# DC_DRIVERS.net
KiCad netlist of a schematic drawn in Altium Designer
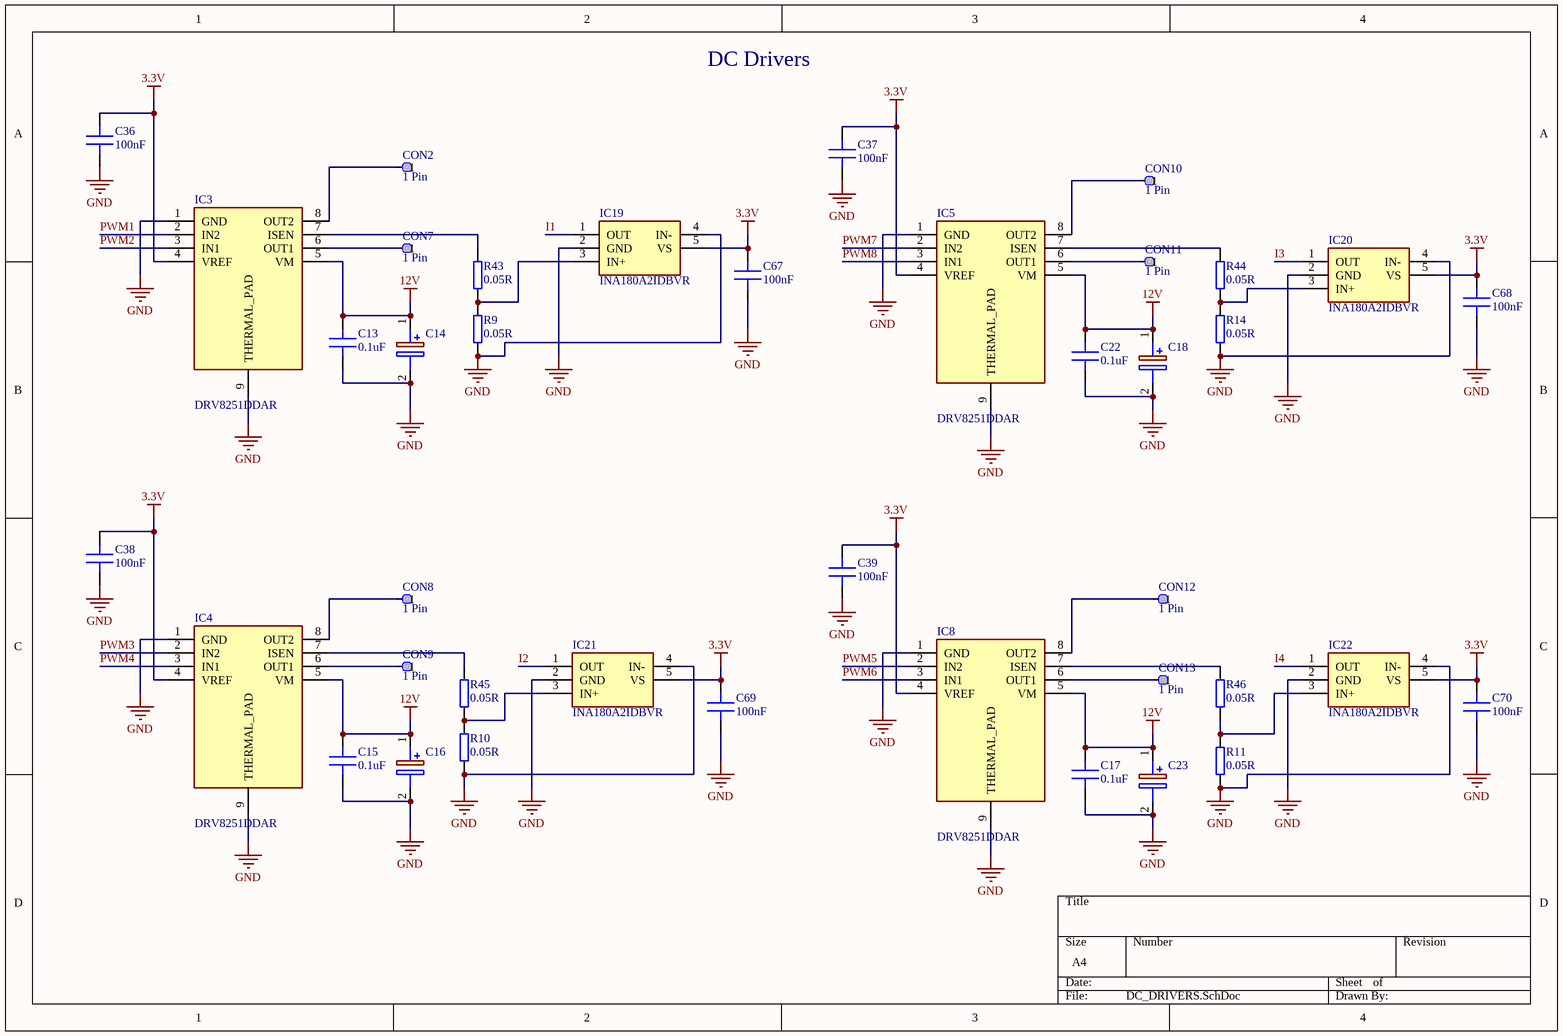
[diagram p0: DC_DRIVERS.SchDoc]

(export (version "E")
  (design (tool "Eeschema 10.0.6"))
  (components
    (comp (ref "C13")
      (value "0.1uF")
      (footprint "C 0402")
      (description "MLCC Capacitor")
      (libsource (lib "Components") (part "Capacitor"))
    )
    (comp (ref "C14")
      (value "UVY1V101MED1TD")
      (footprint "SamacSys:CAPPRD250W50D655H1250")
      (description "Capacitor Polarised")
      (libsource (lib "caravan_sch_lib") (part "UVY1V101MED1TD"))
    )
    (comp (ref "C15")
      (value "0.1uF")
      (footprint "C 0603")
      (description "MLCC Capacitor")
      (libsource (lib "Components") (part "Capacitor"))
    )
    (comp (ref "C16")
      (value "UVY1V101MED1TD")
      (footprint "SamacSys:CAPPRD250W50D655H1250")
      (description "Capacitor Polarised")
      (libsource (lib "caravan_sch_lib") (part "UVY1V101MED1TD"))
    )
    (comp (ref "C17")
      (value "0.1uF")
      (footprint "C 0402")
      (description "MLCC Capacitor")
      (libsource (lib "Components") (part "Capacitor"))
    )
    (comp (ref "C18")
      (value "UVY1V101MED1TD")
      (footprint "SamacSys:CAPPRD250W50D655H1250")
      (description "Capacitor Polarised")
      (libsource (lib "caravan_sch_lib") (part "UVY1V101MED1TD"))
    )
    (comp (ref "C22")
      (value "0.1uF")
      (footprint "C 0402")
      (description "MLCC Capacitor")
      (libsource (lib "Components") (part "Capacitor"))
    )
    (comp (ref "C23")
      (value "UVY1V101MED1TD")
      (footprint "SamacSys:CAPPRD250W50D655H1250")
      (description "Capacitor Polarised")
      (libsource (lib "caravan_sch_lib") (part "UVY1V101MED1TD"))
    )
    (comp (ref "C36")
      (value "100nF")
      (footprint "C 0402")
      (description "MLCC Capacitor")
      (libsource (lib "Components") (part "Capacitor"))
    )
    (comp (ref "C37")
      (value "100nF")
      (footprint "C 0402")
      (description "MLCC Capacitor")
      (libsource (lib "Components") (part "Capacitor"))
    )
    (comp (ref "C38")
      (value "100nF")
      (footprint "C 0402")
      (description "MLCC Capacitor")
      (libsource (lib "Components") (part "Capacitor"))
    )
    (comp (ref "C39")
      (value "100nF")
      (footprint "C 0402")
      (description "MLCC Capacitor")
      (libsource (lib "Components") (part "Capacitor"))
    )
    (comp (ref "C67")
      (value "100nF")
      (footprint "C 0402")
      (description "MLCC Capacitor")
      (libsource (lib "Components") (part "Capacitor"))
    )
    (comp (ref "C68")
      (value "100nF")
      (footprint "C 0402")
      (description "MLCC Capacitor")
      (libsource (lib "Components") (part "Capacitor"))
    )
    (comp (ref "C69")
      (value "100nF")
      (footprint "C 0402")
      (description "MLCC Capacitor")
      (libsource (lib "Components") (part "Capacitor"))
    )
    (comp (ref "C70")
      (value "100nF")
      (footprint "C 0402")
      (description "MLCC Capacitor")
      (libsource (lib "Components") (part "Capacitor"))
    )
    (comp (ref "CON2") (value "1 Pin") (footprint "SMD PAD") (libsource (lib "Connectors") (part "1 Pin")))
    (comp (ref "CON7") (value "1 Pin") (footprint "SMD PAD") (libsource (lib "Connectors") (part "1 Pin")))
    (comp (ref "CON8") (value "1 Pin") (footprint "SMD PAD") (libsource (lib "Connectors") (part "1 Pin")))
    (comp (ref "CON9") (value "1 Pin") (footprint "SMD PAD") (libsource (lib "Connectors") (part "1 Pin")))
    (comp (ref "CON10") (value "1 Pin") (footprint "SMD PAD") (libsource (lib "Connectors") (part "1 Pin")))
    (comp (ref "CON11") (value "1 Pin") (footprint "SMD PAD") (libsource (lib "Connectors") (part "1 Pin")))
    (comp (ref "CON12") (value "1 Pin") (footprint "SMD PAD") (libsource (lib "Connectors") (part "1 Pin")))
    (comp (ref "CON13") (value "1 Pin") (footprint "SMD PAD") (libsource (lib "Connectors") (part "1 Pin")))
    (comp (ref "IC3")
      (value "DRV8251DDAR")
      (footprint "SamacSys:SOIC127P600X170-9N")
      (description "Integrated Circuit")
      (fields (field (name "MOUSER PART NUMBER") "595-DRV8251DDAR"))
      (libsource (lib "caravan_sch_lib") (part "DRV8251DDAR"))
    )
    (comp (ref "IC4")
      (value "DRV8251DDAR")
      (footprint "SamacSys:SOIC127P600X170-9N")
      (description "Integrated Circuit")
      (fields (field (name "MOUSER PART NUMBER") "595-DRV8251DDAR"))
      (libsource (lib "caravan_sch_lib") (part "DRV8251DDAR"))
    )
    (comp (ref "IC5")
      (value "DRV8251DDAR")
      (footprint "SamacSys:SOIC127P600X170-9N")
      (description "Integrated Circuit")
      (fields (field (name "MOUSER PART NUMBER") "595-DRV8251DDAR"))
      (libsource (lib "caravan_sch_lib") (part "DRV8251DDAR"))
    )
    (comp (ref "IC8")
      (value "DRV8251DDAR")
      (footprint "SamacSys:SOIC127P600X170-9N")
      (description "Integrated Circuit")
      (fields (field (name "MOUSER PART NUMBER") "595-DRV8251DDAR"))
      (libsource (lib "caravan_sch_lib") (part "DRV8251DDAR"))
    )
    (comp (ref "IC19")
      (value "INA180A2IDBVR")
      (footprint "SamacSys:SOT95P280X145-5N")
      (description "Integrated Circuit")
      (fields (field (name "MOUSER PART NUMBER") "595-INA180A2IDBVR"))
      (libsource (lib "caravan_sch_lib") (part "INA180A2IDBVR"))
    )
    (comp (ref "IC20")
      (value "INA180A2IDBVR")
      (footprint "SamacSys:SOT95P280X145-5N")
      (description "Integrated Circuit")
      (fields (field (name "MOUSER PART NUMBER") "595-INA180A2IDBVR"))
      (libsource (lib "caravan_sch_lib") (part "INA180A2IDBVR"))
    )
    (comp (ref "IC21")
      (value "INA180A2IDBVR")
      (footprint "SamacSys:SOT95P280X145-5N")
      (description "Integrated Circuit")
      (fields (field (name "MOUSER PART NUMBER") "595-INA180A2IDBVR"))
      (libsource (lib "caravan_sch_lib") (part "INA180A2IDBVR"))
    )
    (comp (ref "IC22")
      (value "INA180A2IDBVR")
      (footprint "SamacSys:SOT95P280X145-5N")
      (description "Integrated Circuit")
      (fields (field (name "MOUSER PART NUMBER") "595-INA180A2IDBVR"))
      (libsource (lib "caravan_sch_lib") (part "INA180A2IDBVR"))
    )
    (comp (ref "R9")
      (value "0.05R")
      (footprint "R 1206")
      (description "General pourpouse resistor")
      (libsource (lib "Components") (part "Resistor"))
    )
    (comp (ref "R10")
      (value "0.05R")
      (footprint "R 1206")
      (description "General pourpouse resistor")
      (libsource (lib "Components") (part "Resistor"))
    )
    (comp (ref "R11")
      (value "0.05R")
      (footprint "R 1206")
      (description "General pourpouse resistor")
      (libsource (lib "Components") (part "Resistor"))
    )
    (comp (ref "R14")
      (value "0.05R")
      (footprint "R 1206")
      (description "General pourpouse resistor")
      (libsource (lib "Components") (part "Resistor"))
    )
    (comp (ref "R43")
      (value "0.05R")
      (footprint "R 1206")
      (description "General pourpouse resistor")
      (libsource (lib "Components") (part "Resistor"))
    )
    (comp (ref "R44")
      (value "0.05R")
      (footprint "R 1206")
      (description "General pourpouse resistor")
      (libsource (lib "Components") (part "Resistor"))
    )
    (comp (ref "R45")
      (value "0.05R")
      (footprint "R 1206")
      (description "General pourpouse resistor")
      (libsource (lib "Components") (part "Resistor"))
    )
    (comp (ref "R46")
      (value "0.05R")
      (footprint "R 1206")
      (description "General pourpouse resistor")
      (libsource (lib "Components") (part "Resistor"))
    )
  )
  (nets
    (net (code "1") (name "/I1") (class "Default")
      (node (ref "IC19") (pin "1") (pinfunction "OUT_1") (pintype "passive"))
    )
    (net (code "2") (name "/I2") (class "Default")
      (node (ref "IC21") (pin "1") (pinfunction "OUT_1") (pintype "passive"))
    )
    (net (code "3") (name "/I3") (class "Default")
      (node (ref "IC20") (pin "1") (pinfunction "OUT_1") (pintype "passive"))
    )
    (net (code "4") (name "/I4") (class "Default")
      (node (ref "IC22") (pin "1") (pinfunction "OUT_1") (pintype "passive"))
    )
    (net (code "5") (name "/PWM1") (class "Default")
      (node (ref "IC3") (pin "2") (pinfunction "IN2_2") (pintype "passive"))
    )
    (net (code "6") (name "/PWM2") (class "Default")
      (node (ref "IC3") (pin "3") (pinfunction "IN1_3") (pintype "passive"))
    )
    (net (code "7") (name "/PWM3") (class "Default")
      (node (ref "IC4") (pin "2") (pinfunction "IN2_2") (pintype "passive"))
    )
    (net (code "8") (name "/PWM4") (class "Default")
      (node (ref "IC4") (pin "3") (pinfunction "IN1_3") (pintype "passive"))
    )
    (net (code "9") (name "/PWM5") (class "Default")
      (node (ref "IC8") (pin "2") (pinfunction "IN2_2") (pintype "passive"))
    )
    (net (code "10") (name "/PWM6") (class "Default")
      (node (ref "IC8") (pin "3") (pinfunction "IN1_3") (pintype "passive"))
    )
    (net (code "11") (name "/PWM7") (class "Default")
      (node (ref "IC5") (pin "2") (pinfunction "IN2_2") (pintype "passive"))
    )
    (net (code "12") (name "/PWM8") (class "Default")
      (node (ref "IC5") (pin "3") (pinfunction "IN1_3") (pintype "passive"))
    )
    (net (code "13") (name "3.3V") (class "Default")
      (node (ref "C36") (pin "1") (pinfunction "1_1") (pintype "passive"))
      (node (ref "C37") (pin "1") (pinfunction "1_1") (pintype "passive"))
      (node (ref "C38") (pin "1") (pinfunction "1_1") (pintype "passive"))
      (node (ref "C39") (pin "1") (pinfunction "1_1") (pintype "passive"))
      (node (ref "C67") (pin "1") (pinfunction "1_1") (pintype "passive"))
      (node (ref "C68") (pin "1") (pinfunction "1_1") (pintype "passive"))
      (node (ref "C69") (pin "1") (pinfunction "1_1") (pintype "passive"))
      (node (ref "C70") (pin "1") (pinfunction "1_1") (pintype "passive"))
      (node (ref "IC19") (pin "5") (pinfunction "VS_5") (pintype "passive"))
      (node (ref "IC20") (pin "5") (pinfunction "VS_5") (pintype "passive"))
      (node (ref "IC21") (pin "5") (pinfunction "VS_5") (pintype "passive"))
      (node (ref "IC22") (pin "5") (pinfunction "VS_5") (pintype "passive"))
      (node (ref "IC3") (pin "4") (pinfunction "VREF_4") (pintype "passive"))
      (node (ref "IC4") (pin "4") (pinfunction "VREF_4") (pintype "passive"))
      (node (ref "IC5") (pin "4") (pinfunction "VREF_4") (pintype "passive"))
      (node (ref "IC8") (pin "4") (pinfunction "VREF_4") (pintype "passive"))
    )
    (net (code "14") (name "12V") (class "Default")
      (node (ref "C13") (pin "1") (pinfunction "1_1") (pintype "passive"))
      (node (ref "C14") (pin "1") (pinfunction "+_1") (pintype "passive"))
      (node (ref "C15") (pin "1") (pinfunction "1_1") (pintype "passive"))
      (node (ref "C16") (pin "1") (pinfunction "+_1") (pintype "passive"))
      (node (ref "C17") (pin "1") (pinfunction "1_1") (pintype "passive"))
      (node (ref "C18") (pin "1") (pinfunction "+_1") (pintype "passive"))
      (node (ref "C22") (pin "1") (pinfunction "1_1") (pintype "passive"))
      (node (ref "C23") (pin "1") (pinfunction "+_1") (pintype "passive"))
      (node (ref "IC3") (pin "5") (pinfunction "VM_5") (pintype "passive"))
      (node (ref "IC4") (pin "5") (pinfunction "VM_5") (pintype "passive"))
      (node (ref "IC5") (pin "5") (pinfunction "VM_5") (pintype "passive"))
      (node (ref "IC8") (pin "5") (pinfunction "VM_5") (pintype "passive"))
    )
    (net (code "15") (name "GND") (class "Default")
      (node (ref "C13") (pin "2") (pinfunction "2_2") (pintype "passive"))
      (node (ref "C14") (pin "2") (pinfunction "-_2") (pintype "passive"))
      (node (ref "C15") (pin "2") (pinfunction "2_2") (pintype "passive"))
      (node (ref "C16") (pin "2") (pinfunction "-_2") (pintype "passive"))
      (node (ref "C17") (pin "2") (pinfunction "2_2") (pintype "passive"))
      (node (ref "C18") (pin "2") (pinfunction "-_2") (pintype "passive"))
      (node (ref "C22") (pin "2") (pinfunction "2_2") (pintype "passive"))
      (node (ref "C23") (pin "2") (pinfunction "-_2") (pintype "passive"))
      (node (ref "C36") (pin "2") (pinfunction "2_2") (pintype "passive"))
      (node (ref "C37") (pin "2") (pinfunction "2_2") (pintype "passive"))
      (node (ref "C38") (pin "2") (pinfunction "2_2") (pintype "passive"))
      (node (ref "C39") (pin "2") (pinfunction "2_2") (pintype "passive"))
      (node (ref "C67") (pin "2") (pinfunction "2_2") (pintype "passive"))
      (node (ref "C68") (pin "2") (pinfunction "2_2") (pintype "passive"))
      (node (ref "C69") (pin "2") (pinfunction "2_2") (pintype "passive"))
      (node (ref "C70") (pin "2") (pinfunction "2_2") (pintype "passive"))
      (node (ref "IC19") (pin "2") (pinfunction "GND_2") (pintype "passive"))
      (node (ref "IC19") (pin "4") (pinfunction "IN-_4") (pintype "passive"))
      (node (ref "IC20") (pin "2") (pinfunction "GND_2") (pintype "passive"))
      (node (ref "IC20") (pin "4") (pinfunction "IN-_4") (pintype "passive"))
      (node (ref "IC21") (pin "2") (pinfunction "GND_2") (pintype "passive"))
      (node (ref "IC21") (pin "4") (pinfunction "IN-_4") (pintype "passive"))
      (node (ref "IC22") (pin "2") (pinfunction "GND_2") (pintype "passive"))
      (node (ref "IC22") (pin "4") (pinfunction "IN-_4") (pintype "passive"))
      (node (ref "IC3") (pin "1") (pinfunction "GND_1") (pintype "passive"))
      (node (ref "IC3") (pin "9") (pinfunction "THERMAL_PAD_9") (pintype "passive"))
      (node (ref "IC4") (pin "1") (pinfunction "GND_1") (pintype "passive"))
      (node (ref "IC4") (pin "9") (pinfunction "THERMAL_PAD_9") (pintype "passive"))
      (node (ref "IC5") (pin "1") (pinfunction "GND_1") (pintype "passive"))
      (node (ref "IC5") (pin "9") (pinfunction "THERMAL_PAD_9") (pintype "passive"))
      (node (ref "IC8") (pin "1") (pinfunction "GND_1") (pintype "passive"))
      (node (ref "IC8") (pin "9") (pinfunction "THERMAL_PAD_9") (pintype "passive"))
      (node (ref "R10") (pin "2") (pinfunction "2_2") (pintype "passive"))
      (node (ref "R11") (pin "2") (pinfunction "2_2") (pintype "passive"))
      (node (ref "R14") (pin "2") (pinfunction "2_2") (pintype "passive"))
      (node (ref "R9") (pin "2") (pinfunction "2_2") (pintype "passive"))
    )
    (net (code "16") (name "Net-(IC3-ISEN)") (class "Default")
      (node (ref "IC3") (pin "7") (pinfunction "ISEN_7") (pintype "passive"))
      (node (ref "R43") (pin "1") (pinfunction "1_1") (pintype "passive"))
    )
    (net (code "17") (name "Net-(IC3-OUT1)") (class "Default")
      (node (ref "CON7") (pin "1") (pinfunction "1_1") (pintype "passive"))
      (node (ref "IC3") (pin "6") (pinfunction "OUT1_6") (pintype "passive"))
    )
    (net (code "18") (name "Net-(IC3-OUT2)") (class "Default")
      (node (ref "CON2") (pin "1") (pinfunction "1_1") (pintype "passive"))
      (node (ref "IC3") (pin "8") (pinfunction "OUT2_8") (pintype "passive"))
    )
    (net (code "19") (name "Net-(IC4-ISEN)") (class "Default")
      (node (ref "IC4") (pin "7") (pinfunction "ISEN_7") (pintype "passive"))
      (node (ref "R45") (pin "1") (pinfunction "1_1") (pintype "passive"))
    )
    (net (code "20") (name "Net-(IC4-OUT1)") (class "Default")
      (node (ref "CON9") (pin "1") (pinfunction "1_1") (pintype "passive"))
      (node (ref "IC4") (pin "6") (pinfunction "OUT1_6") (pintype "passive"))
    )
    (net (code "21") (name "Net-(IC4-OUT2)") (class "Default")
      (node (ref "CON8") (pin "1") (pinfunction "1_1") (pintype "passive"))
      (node (ref "IC4") (pin "8") (pinfunction "OUT2_8") (pintype "passive"))
    )
    (net (code "22") (name "Net-(IC5-ISEN)") (class "Default")
      (node (ref "IC5") (pin "7") (pinfunction "ISEN_7") (pintype "passive"))
      (node (ref "R44") (pin "1") (pinfunction "1_1") (pintype "passive"))
    )
    (net (code "23") (name "Net-(IC5-OUT1)") (class "Default")
      (node (ref "CON11") (pin "1") (pinfunction "1_1") (pintype "passive"))
      (node (ref "IC5") (pin "6") (pinfunction "OUT1_6") (pintype "passive"))
    )
    (net (code "24") (name "Net-(IC5-OUT2)") (class "Default")
      (node (ref "CON10") (pin "1") (pinfunction "1_1") (pintype "passive"))
      (node (ref "IC5") (pin "8") (pinfunction "OUT2_8") (pintype "passive"))
    )
    (net (code "25") (name "Net-(IC8-ISEN)") (class "Default")
      (node (ref "IC8") (pin "7") (pinfunction "ISEN_7") (pintype "passive"))
      (node (ref "R46") (pin "1") (pinfunction "1_1") (pintype "passive"))
    )
    (net (code "26") (name "Net-(IC8-OUT1)") (class "Default")
      (node (ref "CON13") (pin "1") (pinfunction "1_1") (pintype "passive"))
      (node (ref "IC8") (pin "6") (pinfunction "OUT1_6") (pintype "passive"))
    )
    (net (code "27") (name "Net-(IC8-OUT2)") (class "Default")
      (node (ref "CON12") (pin "1") (pinfunction "1_1") (pintype "passive"))
      (node (ref "IC8") (pin "8") (pinfunction "OUT2_8") (pintype "passive"))
    )
    (net (code "28") (name "Net-(IC19-IN+)") (class "Default")
      (node (ref "IC19") (pin "3") (pinfunction "IN+_3") (pintype "passive"))
      (node (ref "R43") (pin "2") (pinfunction "2_2") (pintype "passive"))
      (node (ref "R9") (pin "1") (pinfunction "1_1") (pintype "passive"))
    )
    (net (code "29") (name "Net-(IC20-IN+)") (class "Default")
      (node (ref "IC20") (pin "3") (pinfunction "IN+_3") (pintype "passive"))
      (node (ref "R14") (pin "1") (pinfunction "1_1") (pintype "passive"))
      (node (ref "R44") (pin "2") (pinfunction "2_2") (pintype "passive"))
    )
    (net (code "30") (name "Net-(IC21-IN+)") (class "Default")
      (node (ref "IC21") (pin "3") (pinfunction "IN+_3") (pintype "passive"))
      (node (ref "R10") (pin "1") (pinfunction "1_1") (pintype "passive"))
      (node (ref "R45") (pin "2") (pinfunction "2_2") (pintype "passive"))
    )
    (net (code "31") (name "Net-(IC22-IN+)") (class "Default")
      (node (ref "IC22") (pin "3") (pinfunction "IN+_3") (pintype "passive"))
      (node (ref "R11") (pin "1") (pinfunction "1_1") (pintype "passive"))
      (node (ref "R46") (pin "2") (pinfunction "2_2") (pintype "passive"))
    )
  )
)
